# Display4s.net
KiCad netlist of a schematic drawn in EAGLE
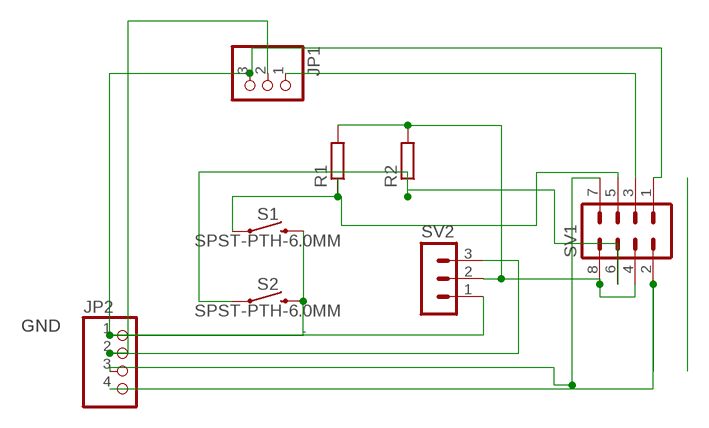
[diagram p0: schematic, sheet 1]

(export (version "E")
  (design (tool "Eeschema 10.0.6"))
  (components
    (comp (ref "JP1")
      (value "PINHD-1X3")
      (footprint "eagle-import:1X03")
      (libsource (lib "eagle-import") (part "PINHD-1X3"))
    )
    (comp (ref "JP2")
      (value "PINHD-1X4")
      (footprint "eagle-import:1X04")
      (libsource (lib "eagle-import") (part "PINHD-1X4"))
    )
    (comp (ref "R1")
      (value "R-EU_0207/10")
      (footprint "eagle-import:0207_10")
      (libsource (lib "eagle-import") (part "R-EU_0207/10"))
    )
    (comp (ref "R2")
      (value "R-EU_0207/10")
      (footprint "eagle-import:0207_10")
      (libsource (lib "eagle-import") (part "R-EU_0207/10"))
    )
    (comp (ref "S1")
      (value "SPST-PTH-6.0MM")
      (footprint "eagle-import:TACTILE_SWITCH_PTH_6.0MM")
      (libsource (lib "eagle-import") (part "MOMENTARY-SWITCH-SPST-PTH-6.0MM"))
    )
    (comp (ref "S2")
      (value "SPST-PTH-6.0MM")
      (footprint "eagle-import:TACTILE_SWITCH_PTH_6.0MM")
      (libsource (lib "eagle-import") (part "MOMENTARY-SWITCH-SPST-PTH-6.0MM"))
    )
    (comp (ref "SV1")
      (value "MA04-2")
      (footprint "eagle-import:MA04-2")
      (libsource (lib "eagle-import") (part "MA04-2"))
    )
    (comp (ref "SV2")
      (value "MA03-1")
      (footprint "eagle-import:MA03-1")
      (libsource (lib "eagle-import") (part "MA03-1"))
    )
  )
  (nets
    (net (code "1") (name "/GND") (class "Default")
      (node (ref "JP1") (pin "3") (pinfunction "3_3") (pintype "passive"))
      (node (ref "JP2") (pin "1") (pinfunction "1_1") (pintype "passive"))
      (node (ref "S1") (pin "3") (pinfunction "2_3") (pintype "passive"))
      (node (ref "S2") (pin "3") (pinfunction "2_3") (pintype "passive"))
      (node (ref "SV1") (pin "1") (pinfunction "1_1") (pintype "passive"))
      (node (ref "SV2") (pin "1") (pinfunction "1_1") (pintype "passive"))
    )
    (net (code "2") (name "Net-(JP1-Pad1)") (class "Default")
      (node (ref "JP1") (pin "1") (pinfunction "1_1") (pintype "passive"))
      (node (ref "SV1") (pin "3") (pinfunction "3_3") (pintype "passive"))
    )
    (net (code "3") (name "Net-(JP1-Pad2)") (class "Default")
      (node (ref "JP1") (pin "2") (pinfunction "2_2") (pintype "passive"))
      (node (ref "JP2") (pin "2") (pinfunction "2_2") (pintype "passive"))
      (node (ref "SV2") (pin "3") (pinfunction "3_3") (pintype "passive"))
    )
    (net (code "4") (name "Net-(JP2-Pad3)") (class "Default")
      (node (ref "JP2") (pin "3") (pinfunction "3_3") (pintype "passive"))
      (node (ref "SV1") (pin "7") (pinfunction "7_7") (pintype "passive"))
    )
    (net (code "5") (name "Net-(JP2-Pad4)") (class "Default")
      (node (ref "JP2") (pin "4") (pinfunction "4_4") (pintype "passive"))
      (node (ref "SV1") (pin "2") (pinfunction "2_2") (pintype "passive"))
    )
    (net (code "6") (name "Net-(R1-Pad1)") (class "Default")
      (node (ref "R1") (pin "1") (pinfunction "1_1") (pintype "passive"))
      (node (ref "S1") (pin "1") (pinfunction "1_1") (pintype "passive"))
      (node (ref "SV1") (pin "5") (pinfunction "5_5") (pintype "passive"))
    )
    (net (code "7") (name "Net-(R1-Pad2)") (class "Default")
      (node (ref "R1") (pin "2") (pinfunction "2_2") (pintype "passive"))
      (node (ref "R2") (pin "2") (pinfunction "2_2") (pintype "passive"))
      (node (ref "SV1") (pin "4") (pinfunction "4_4") (pintype "passive"))
      (node (ref "SV1") (pin "8") (pinfunction "8_8") (pintype "passive"))
      (node (ref "SV2") (pin "2") (pinfunction "2_2") (pintype "passive"))
    )
    (net (code "8") (name "Net-(R2-Pad1)") (class "Default")
      (node (ref "R2") (pin "1") (pinfunction "1_1") (pintype "passive"))
      (node (ref "S2") (pin "1") (pinfunction "1_1") (pintype "passive"))
      (node (ref "SV1") (pin "6") (pinfunction "6_6") (pintype "passive"))
    )
  )
)
